# EspProg-V1_0.net
KiCad netlist of a schematic drawn in Altium Designer
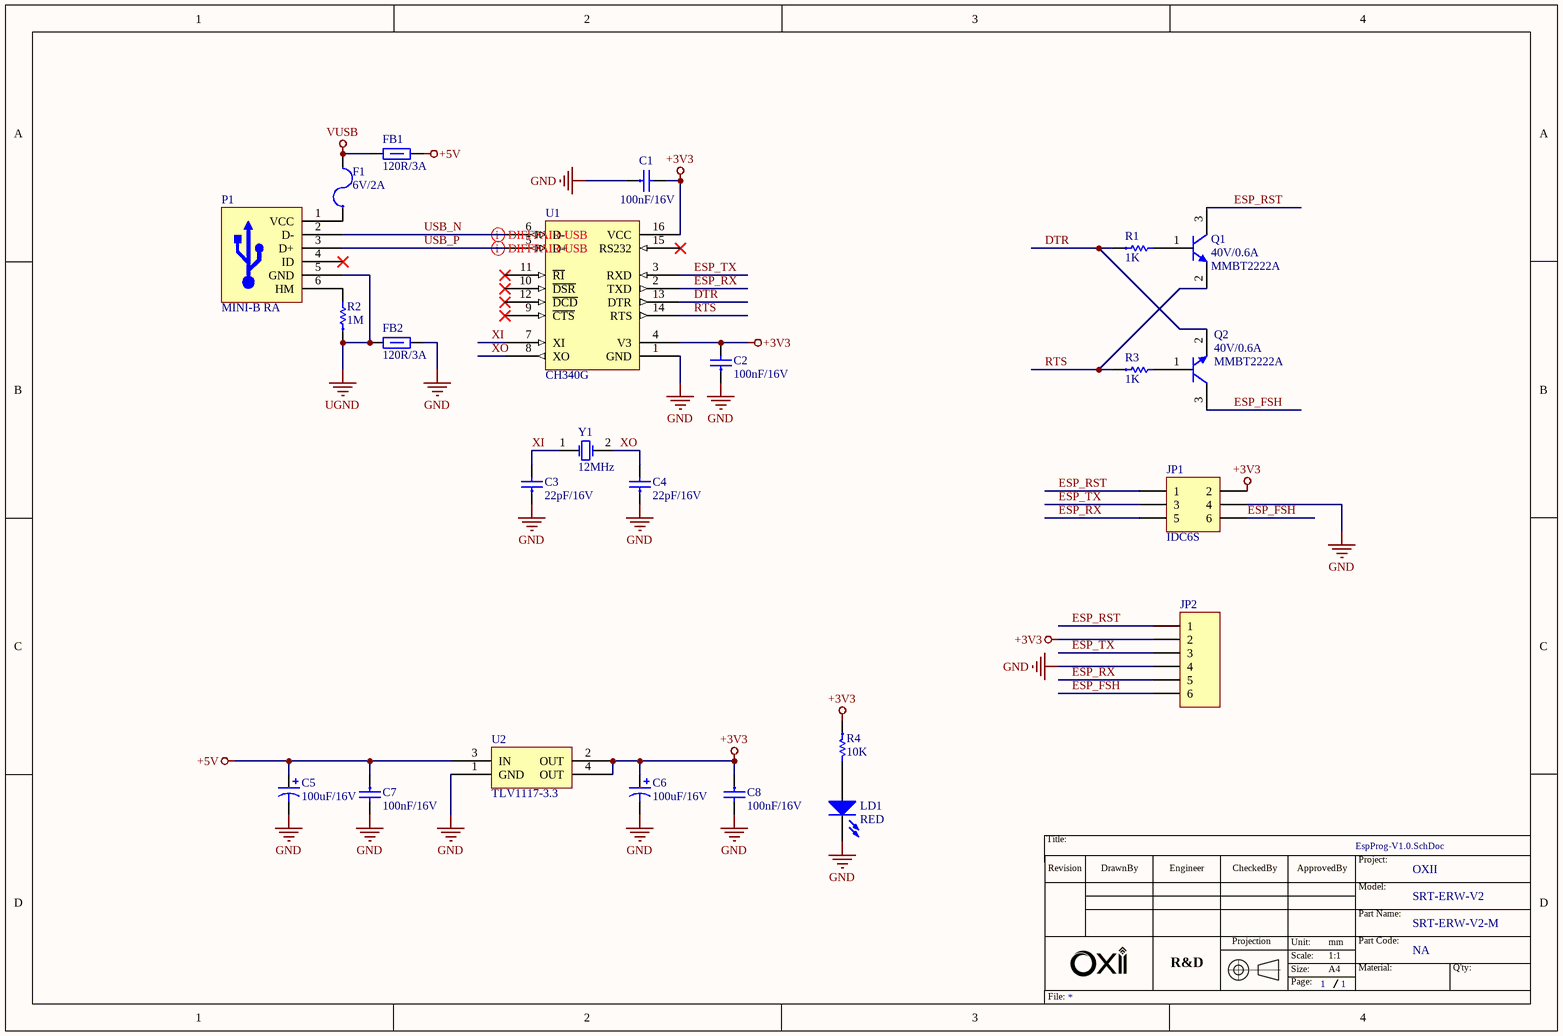
[diagram p0: EspProg-V1.0.SchDoc]

(export (version "E")
  (design (tool "Eeschema 10.0.6"))
  (components
    (comp (ref "C1")
      (value "100nF/16V")
      (footprint "CAP-CER0603-0.8H")
      (description "CAP CER 100nF/16V 10% X7R 0603 SMD")
      (fields (field (name "MFR") "YAGEO"))
      (libsource (lib "ADLibEP") (part "CAPCER0008 0603 100nF/16V"))
    )
    (comp (ref "C2")
      (value "100nF/16V")
      (footprint "CAP-CER0603-0.8H")
      (description "CAP CER 100nF/16V 10% X7R 0603 SMD")
      (fields (field (name "MFR") "YAGEO"))
      (libsource (lib "ADLibEP") (part "CAPCER0008 0603 100nF/16V"))
    )
    (comp (ref "C3")
      (value "22pF/16V")
      (footprint "CAP-CER0603-0.8H")
      (description "CAP CER 22pF/16V 5% C0G 0603 SMD")
      (fields (field (name "MFR") "KEMET"))
      (libsource (lib "ADLibEP") (part "CAPCER0060 0603 22pF/16V"))
    )
    (comp (ref "C4")
      (value "22pF/16V")
      (footprint "CAP-CER0603-0.8H")
      (description "CAP CER 22pF/16V 5% C0G 0603 SMD")
      (fields (field (name "MFR") "KEMET"))
      (libsource (lib "ADLibEP") (part "CAPCER0060 0603 22pF/16V"))
    )
    (comp (ref "C5")
      (value "100uF/16V")
      (footprint "CAP-ALU-6.3D5.8H-SMD")
      (description "CAP ALU 100uF/16V 20% 2K105 2.2P 6.3X5.8 SMD")
      (fields (field (name "MFR") "NICHICON"))
      (libsource (lib "ADLibEP") (part "CAPALU0012 6.3X5.8 100uF/16V SMD"))
    )
    (comp (ref "C6")
      (value "100uF/16V")
      (footprint "CAP-ALU-6.3D5.8H-SMD")
      (description "CAP ALU 100uF/16V 20% 2K105 2.2P 6.3X5.8 SMD")
      (fields (field (name "MFR") "NICHICON"))
      (libsource (lib "ADLibEP") (part "CAPALU0012 6.3X5.8 100uF/16V SMD"))
    )
    (comp (ref "C7")
      (value "100nF/16V")
      (footprint "CAP-CER0603-0.8H")
      (description "CAP CER 100nF/16V 10% X7R 0603 SMD")
      (fields (field (name "MFR") "YAGEO"))
      (libsource (lib "ADLibEP") (part "CAPCER0008 0603 100nF/16V"))
    )
    (comp (ref "C8")
      (value "100nF/16V")
      (footprint "CAP-CER0603-0.8H")
      (description "CAP CER 100nF/16V 10% X7R 0603 SMD")
      (fields (field (name "MFR") "YAGEO"))
      (libsource (lib "ADLibEP") (part "CAPCER0008 0603 100nF/16V"))
    )
    (comp (ref "F1")
      (value "6V/2A")
      (footprint "FUS-PTC-SMD1206-1.6H")
      (description "FUS PTC RST 6V 2A 1206 SMD")
      (fields (field (name "MFR") "BOURNS"))
      (libsource (lib "ADLibEP") (part "FUSPTC0001 1206 6V/2A"))
    )
    (comp (ref "FB1")
      (value "120R/3A")
      (footprint "IND-C0805-1.1H")
      (description "FIL FER CHP 1LN 120R 3A 0805 SMD")
      (fields (field (name "MFR") "MURATA"))
      (libsource (lib "ADLibEP") (part "FILFER0001 0805 120R/3A"))
    )
    (comp (ref "FB2")
      (value "120R/3A")
      (footprint "IND-C0805-1.1H")
      (description "FIL FER CHP 1LN 120R 3A 0805 SMD")
      (fields (field (name "MFR") "MURATA"))
      (libsource (lib "ADLibEP") (part "FILFER0001 0805 120R/3A"))
    )
    (comp (ref "JP1")
      (value "IDC6S")
      (footprint "CON-IDC6-2.54P9.3H-S-THR")
      (description "CON W2B IDC2.54M-2X3V-9H THR")
      (fields (field (name "MFR") "XFCN"))
      (libsource (lib "ADLibEP") (part "CONW2B0010 IDC2.54M-6PV"))
    )
    (comp (ref "JP2")
      (value "XH2.54M-1X06V-7H")
      (footprint "CON-XH2.54-6S")
      (description "CON B2B XH2.54M-1X06V-7H THR")
      (fields (field (name "MFR") "XUNPU"))
      (libsource (lib "ADLibEP") (part "CONW2B0005 XH2.54M-1X06V-7H"))
    )
    (comp (ref "LD1")
      (value "RED")
      (footprint "LED-IND0603-RED-0.6H")
      (description "LED IND RED CLR 2V 20mA 0603 SMD")
      (fields (field (name "MFR") "WURTH"))
      (libsource (lib "ADLibEP") (part "LEDIND0001 0603 RED"))
    )
    (comp (ref "P1")
      (value "MINI-B RA")
      (footprint "CON-USB-MINIB-SMD")
      (description "CON USB TYPB RCPT 5POS MINI-B RA SMD")
      (fields (field (name "MFR") "HANBO"))
      (libsource (lib "ADLibEP") (part "CONUSB0001 MINI-B RA SMD"))
    )
    (comp (ref "Q1")
      (value "40V/0.6A")
      (footprint "SOT23-3-1.1H")
      (description "BJT NPN 40V 0.6A SOT23-3 SMD")
      (fields (field (name "NOTE") "MMBT2222A") (field (name "MFR") "ONSEMI"))
      (libsource (lib "ADLibEP") (part "BJTNPN0001 SOT23 40V/0.6A"))
    )
    (comp (ref "Q2")
      (value "40V/0.6A")
      (footprint "SOT23-3-1.1H")
      (description "BJT NPN 40V 0.6A SOT23-3 SMD")
      (fields (field (name "NOTE") "MMBT2222A") (field (name "MFR") "ONSEMI"))
      (libsource (lib "ADLibEP") (part "BJTNPN0001 SOT23 40V/0.6A"))
    )
    (comp (ref "R1")
      (value "1K")
      (footprint "RES-CHP0603-0.6H")
      (description "RES CHP 1K 1% 1/10W 0603 SMD")
      (fields (field (name "MFR") "YAGEO"))
      (libsource (lib "ADLibEP") (part "RESCHP0007 0603 1% 1K"))
    )
    (comp (ref "R2")
      (value "1M")
      (footprint "RES-CHP0603-0.6H")
      (description "RES CHP 1M 1% 1/10W 0603 SMD")
      (fields (field (name "MFR") "YAGEO"))
      (libsource (lib "ADLibEP") (part "RESCHP0036 0603 1% 1M"))
    )
    (comp (ref "R3")
      (value "1K")
      (footprint "RES-CHP0603-0.6H")
      (description "RES CHP 1K 1% 1/10W 0603 SMD")
      (fields (field (name "MFR") "YAGEO"))
      (libsource (lib "ADLibEP") (part "RESCHP0007 0603 1% 1K"))
    )
    (comp (ref "R4")
      (value "10K")
      (footprint "RES-CHP0603-0.6H")
      (description "RES CHP 10K 1% 1/10W 0603 SMD")
      (fields (field (name "MFR") "YAGEO"))
      (libsource (lib "ADLibEP") (part "RESCHP0008 0603 1% 10K"))
    )
    (comp (ref "U1")
      (value "CH340G")
      (footprint "SOIC16-1.75H")
      (description "ICS INT USB-TTL CH340G 16SOIC SMD")
      (fields (field (name "MFR") "WCH"))
      (libsource (lib "ADLibEP") (part "ICSINT0001 CH340G"))
    )
    (comp (ref "U2")
      (value "TLV1117-3.3")
      (footprint "SOT223-4N-1.8H")
      (description "ICS VRE TLV1117-33 3V3 0.8A SOT223 SMD")
      (fields (field (name "MFR") "TI"))
      (libsource (lib "ADLibEP") (part "ICSVRE0001 SOT223 TLV1117-3.3"))
    )
    (comp (ref "Y1")
      (value "12MHz")
      (footprint "XTAL-HC49S-3.5H-THR")
      (description "XTA CRY 12MHz 20pF 10PPM HC49S THR")
      (fields (field (name "MFR") "YXC"))
      (libsource (lib "ADLibEP") (part "XTACRY0006 HC49S-THR 12MHz"))
    )
  )
  (nets
    (net (code "1") (name "+3V3") (class "Default")
      (node (ref "C1") (pin "2") (pinfunction "2_2") (pintype "passive"))
      (node (ref "C2") (pin "2") (pinfunction "2_2") (pintype "passive"))
      (node (ref "C6") (pin "1") (pinfunction "1_1") (pintype "passive"))
      (node (ref "C8") (pin "1") (pinfunction "1_1") (pintype "passive"))
      (node (ref "JP1") (pin "2") (pinfunction "2_2") (pintype "passive"))
      (node (ref "JP2") (pin "2") (pinfunction "2_2") (pintype "passive"))
      (node (ref "R4") (pin "1") (pinfunction "1_1") (pintype "passive"))
      (node (ref "U1") (pin "16") (pinfunction "VCC_16") (pintype "power_in"))
      (node (ref "U1") (pin "4") (pinfunction "V3_4") (pintype "power_in"))
      (node (ref "U2") (pin "2") (pinfunction "OUT_2") (pintype "passive"))
      (node (ref "U2") (pin "4") (pinfunction "OUT_4") (pintype "passive"))
    )
    (net (code "2") (name "+5V") (class "Default")
      (node (ref "C5") (pin "1") (pinfunction "1_1") (pintype "passive"))
      (node (ref "C7") (pin "1") (pinfunction "1_1") (pintype "passive"))
      (node (ref "FB1") (pin "2") (pinfunction "2_2") (pintype "passive"))
      (node (ref "U2") (pin "3") (pinfunction "IN_3") (pintype "passive"))
    )
    (net (code "3") (name "/DTR") (class "Default")
      (node (ref "Q2") (pin "2") (pinfunction "E_2") (pintype "passive"))
      (node (ref "R1") (pin "1") (pinfunction "1_1") (pintype "passive"))
      (node (ref "U1") (pin "13") (pinfunction "DTR_13") (pintype "output"))
    )
    (net (code "4") (name "/ESP_FSH") (class "Default")
      (node (ref "JP1") (pin "6") (pinfunction "6_6") (pintype "passive"))
      (node (ref "JP2") (pin "6") (pinfunction "6_6") (pintype "passive"))
      (node (ref "Q2") (pin "3") (pinfunction "C_3") (pintype "passive"))
    )
    (net (code "5") (name "/ESP_RST") (class "Default")
      (node (ref "JP1") (pin "1") (pinfunction "1_1") (pintype "passive"))
      (node (ref "JP2") (pin "1") (pinfunction "1_1") (pintype "passive"))
      (node (ref "Q1") (pin "3") (pinfunction "C_3") (pintype "passive"))
    )
    (net (code "6") (name "/ESP_RX") (class "Default")
      (node (ref "JP1") (pin "5") (pinfunction "5_5") (pintype "passive"))
      (node (ref "JP2") (pin "5") (pinfunction "5_5") (pintype "passive"))
      (node (ref "U1") (pin "2") (pinfunction "TXD_2") (pintype "output"))
    )
    (net (code "7") (name "/ESP_TX") (class "Default")
      (node (ref "JP1") (pin "3") (pinfunction "3_3") (pintype "passive"))
      (node (ref "JP2") (pin "3") (pinfunction "3_3") (pintype "passive"))
      (node (ref "U1") (pin "3") (pinfunction "RXD_3") (pintype "input"))
    )
    (net (code "8") (name "/RTS") (class "Default")
      (node (ref "Q1") (pin "2") (pinfunction "E_2") (pintype "passive"))
      (node (ref "R3") (pin "1") (pinfunction "1_1") (pintype "passive"))
      (node (ref "U1") (pin "14") (pinfunction "RTS_14") (pintype "output"))
    )
    (net (code "9") (name "/USB_N") (class "Default")
      (node (ref "P1") (pin "2") (pinfunction "D-_2") (pintype "passive"))
      (node (ref "U1") (pin "6") (pinfunction "D-_6") (pintype "bidirectional"))
    )
    (net (code "10") (name "/USB_P") (class "Default")
      (node (ref "P1") (pin "3") (pinfunction "D+_3") (pintype "passive"))
      (node (ref "U1") (pin "5") (pinfunction "D+_5") (pintype "bidirectional"))
    )
    (net (code "11") (name "/XI") (class "Default")
      (node (ref "C3") (pin "2") (pinfunction "2_2") (pintype "passive"))
      (node (ref "U1") (pin "7") (pinfunction "XI_7") (pintype "input"))
      (node (ref "Y1") (pin "1") (pinfunction "OSC1_1") (pintype "passive"))
    )
    (net (code "12") (name "/XO") (class "Default")
      (node (ref "C4") (pin "2") (pinfunction "2_2") (pintype "passive"))
      (node (ref "U1") (pin "8") (pinfunction "XO_8") (pintype "output"))
      (node (ref "Y1") (pin "2") (pinfunction "OSC2_2") (pintype "passive"))
    )
    (net (code "13") (name "GND") (class "Default")
      (node (ref "C1") (pin "1") (pinfunction "1_1") (pintype "passive"))
      (node (ref "C2") (pin "1") (pinfunction "1_1") (pintype "passive"))
      (node (ref "C3") (pin "1") (pinfunction "1_1") (pintype "passive"))
      (node (ref "C4") (pin "1") (pinfunction "1_1") (pintype "passive"))
      (node (ref "C5") (pin "2") (pinfunction "2_2") (pintype "passive"))
      (node (ref "C6") (pin "2") (pinfunction "2_2") (pintype "passive"))
      (node (ref "C7") (pin "2") (pinfunction "2_2") (pintype "passive"))
      (node (ref "C8") (pin "2") (pinfunction "2_2") (pintype "passive"))
      (node (ref "FB2") (pin "2") (pinfunction "2_2") (pintype "passive"))
      (node (ref "JP1") (pin "4") (pinfunction "4_4") (pintype "passive"))
      (node (ref "JP2") (pin "4") (pinfunction "4_4") (pintype "passive"))
      (node (ref "LD1") (pin "2") (pinfunction "K_2") (pintype "passive"))
      (node (ref "U1") (pin "1") (pinfunction "GND_1") (pintype "power_in"))
      (node (ref "U2") (pin "1") (pinfunction "GND_1") (pintype "passive"))
    )
    (net (code "14") (name "Net-(LD1-A)") (class "Default")
      (node (ref "LD1") (pin "1") (pinfunction "A_1") (pintype "passive"))
      (node (ref "R4") (pin "2") (pinfunction "2_2") (pintype "passive"))
    )
    (net (code "15") (name "Net-(P1-HM)") (class "Default")
      (node (ref "P1") (pin "6") (pinfunction "HM_6") (pintype "passive"))
      (node (ref "R2") (pin "2") (pinfunction "2_2") (pintype "passive"))
    )
    (net (code "16") (name "Net-(P1-VCC)") (class "Default")
      (node (ref "F1") (pin "1") (pinfunction "1_1") (pintype "passive"))
      (node (ref "P1") (pin "1") (pinfunction "VCC_1") (pintype "passive"))
    )
    (net (code "17") (name "Net-(Q1-B)") (class "Default")
      (node (ref "Q1") (pin "1") (pinfunction "B_1") (pintype "passive"))
      (node (ref "R1") (pin "2") (pinfunction "2_2") (pintype "passive"))
    )
    (net (code "18") (name "Net-(Q2-B)") (class "Default")
      (node (ref "Q2") (pin "1") (pinfunction "B_1") (pintype "passive"))
      (node (ref "R3") (pin "2") (pinfunction "2_2") (pintype "passive"))
    )
    (net (code "19") (name "UGND") (class "Default")
      (node (ref "FB2") (pin "1") (pinfunction "1_1") (pintype "passive"))
      (node (ref "P1") (pin "5") (pinfunction "GND_5") (pintype "passive"))
      (node (ref "R2") (pin "1") (pinfunction "1_1") (pintype "passive"))
    )
    (net (code "20") (name "VUSB") (class "Default")
      (node (ref "F1") (pin "2") (pinfunction "2_2") (pintype "passive"))
      (node (ref "FB1") (pin "1") (pinfunction "1_1") (pintype "passive"))
    )
    (net (code "21") (name "unconnected-(P1-ID-Pad4)") (class "Default")
      (node (ref "P1") (pin "4") (pinfunction "ID_4") (pintype "passive+no_connect"))
    )
    (net (code "22") (name "unconnected-(U1-RS232-Pad15)") (class "Default")
      (node (ref "U1") (pin "15") (pinfunction "RS232_15") (pintype "input+no_connect"))
    )
    (net (code "23") (name "unconnected-(U1-~{CTS}-Pad9)") (class "Default")
      (node (ref "U1") (pin "9") (pinfunction "~{CTS}_9") (pintype "input+no_connect"))
    )
    (net (code "24") (name "unconnected-(U1-~{DCD}-Pad12)") (class "Default")
      (node (ref "U1") (pin "12") (pinfunction "~{DCD}_12") (pintype "input+no_connect"))
    )
    (net (code "25") (name "unconnected-(U1-~{DSR}-Pad10)") (class "Default")
      (node (ref "U1") (pin "10") (pinfunction "~{DSR}_10") (pintype "input+no_connect"))
    )
    (net (code "26") (name "unconnected-(U1-~{RI}-Pad11)") (class "Default")
      (node (ref "U1") (pin "11") (pinfunction "~{RI}_11") (pintype "input+no_connect"))
    )
  )
)
